# Cal.net
KiCad netlist of a schematic drawn in Altium Designer
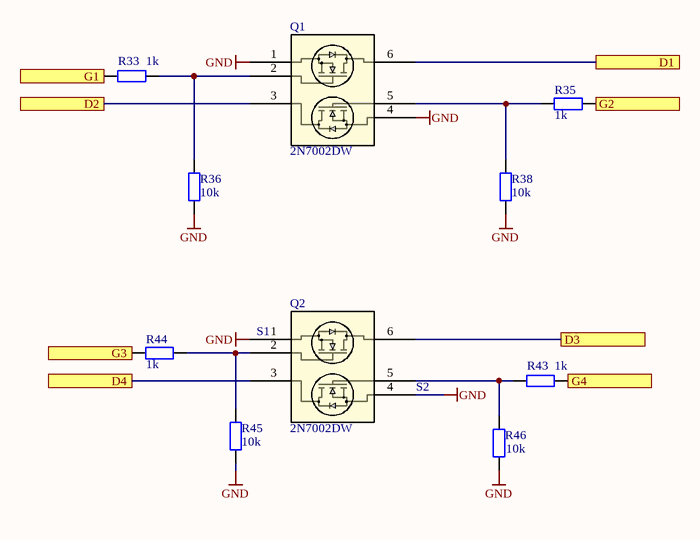
[diagram p0: Cal.SchDoc]

(export (version "E")
  (design (tool "Eeschema 10.0.6"))
  (components
    (comp (ref "Q1")
      (value "2N7002DW")
      (footprint "SC-88SC70-6SOT-363_419B-02_ONS_OSI")
      (description "Description")
      (fields (field (name "COPYRIGHT") "Copyright (C) 2026 Ultra Librarian. All rights reserved."))
      (libsource (lib "2N7002DW") (part "2N7002DW"))
    )
    (comp (ref "Q2")
      (value "2N7002DW")
      (footprint "SC-88SC70-6SOT-363_419B-02_ONS_OSI")
      (description "Description")
      (fields (field (name "COPYRIGHT") "Copyright (C) 2026 Ultra Librarian. All rights reserved."))
      (libsource (lib "2N7002DW") (part "2N7002DW"))
    )
    (comp (ref "R33")
      (value "1k")
      (footprint "C1206-KUE")
      (description "Resistor SMD")
      (fields (field (name "MANUFACTURER") "AVX") (field (name "PUBLISHER") "Altium Limited"))
      (libsource (lib "") (part "ResistorSMD_1"))
    )
    (comp (ref "R35")
      (value "1k")
      (footprint "C1206-KUE")
      (description "Resistor SMD")
      (fields (field (name "MANUFACTURER") "AVX") (field (name "PUBLISHER") "Altium Limited"))
      (libsource (lib "") (part "ResistorSMD_2"))
    )
    (comp (ref "R36")
      (value "10k")
      (footprint "C1206-KUE")
      (description "Resistor SMD")
      (fields (field (name "MANUFACTURER") "AVX") (field (name "PUBLISHER") "Altium Limited"))
      (libsource (lib "ExtrapartsKUE_V01") (part "ResistorSMD"))
    )
    (comp (ref "R38")
      (value "10k")
      (footprint "C1206-KUE")
      (description "Resistor SMD")
      (fields (field (name "MANUFACTURER") "AVX") (field (name "PUBLISHER") "Altium Limited"))
      (libsource (lib "ExtrapartsKUE_V01") (part "ResistorSMD"))
    )
    (comp (ref "R43")
      (value "1k")
      (footprint "C1206-KUE")
      (description "Resistor SMD")
      (fields (field (name "MANUFACTURER") "AVX") (field (name "PUBLISHER") "Altium Limited"))
      (libsource (lib "") (part "ResistorSMD_1"))
    )
    (comp (ref "R44")
      (value "1k")
      (footprint "C1206-KUE")
      (description "Resistor SMD")
      (fields (field (name "MANUFACTURER") "AVX") (field (name "PUBLISHER") "Altium Limited"))
      (libsource (lib "") (part "ResistorSMD_1"))
    )
    (comp (ref "R45")
      (value "10k")
      (footprint "C1206-KUE")
      (description "Resistor SMD")
      (fields (field (name "MANUFACTURER") "AVX") (field (name "PUBLISHER") "Altium Limited"))
      (libsource (lib "ExtrapartsKUE_V01") (part "ResistorSMD"))
    )
    (comp (ref "R46")
      (value "10k")
      (footprint "C1206-KUE")
      (description "Resistor SMD")
      (fields (field (name "MANUFACTURER") "AVX") (field (name "PUBLISHER") "Altium Limited"))
      (libsource (lib "ExtrapartsKUE_V01") (part "ResistorSMD"))
    )
  )
  (nets
    (net (code "1") (name "/D1") (class "Default")
      (node (ref "Q1") (pin "6") (pinfunction "6_6") (pintype "passive"))
    )
    (net (code "2") (name "/D2") (class "Default")
      (node (ref "Q1") (pin "3") (pinfunction "3_3") (pintype "passive"))
    )
    (net (code "3") (name "/D3") (class "Default")
      (node (ref "Q2") (pin "6") (pinfunction "6_6") (pintype "passive"))
    )
    (net (code "4") (name "/D4") (class "Default")
      (node (ref "Q2") (pin "3") (pinfunction "3_3") (pintype "passive"))
    )
    (net (code "5") (name "/G1") (class "Default")
      (node (ref "R33") (pin "2") (pinfunction "2_2") (pintype "passive"))
    )
    (net (code "6") (name "/G2") (class "Default")
      (node (ref "R35") (pin "2") (pinfunction "2_2") (pintype "passive"))
    )
    (net (code "7") (name "/G3") (class "Default")
      (node (ref "R44") (pin "2") (pinfunction "2_2") (pintype "passive"))
    )
    (net (code "8") (name "/G4") (class "Default")
      (node (ref "R43") (pin "1") (pinfunction "1_1") (pintype "passive"))
    )
    (net (code "9") (name "GND") (class "Default")
      (node (ref "Q1") (pin "1") (pinfunction "1_1") (pintype "passive"))
      (node (ref "Q1") (pin "4") (pinfunction "4_4") (pintype "passive"))
      (node (ref "Q2") (pin "1") (pinfunction "1_1") (pintype "passive"))
      (node (ref "Q2") (pin "4") (pinfunction "4_4") (pintype "passive"))
      (node (ref "R36") (pin "2") (pinfunction "2_2") (pintype "passive"))
      (node (ref "R38") (pin "2") (pinfunction "2_2") (pintype "passive"))
      (node (ref "R45") (pin "2") (pinfunction "2_2") (pintype "passive"))
      (node (ref "R46") (pin "2") (pinfunction "2_2") (pintype "passive"))
    )
    (net (code "10") (name "Net-(Q1-Pad2)") (class "Default")
      (node (ref "Q1") (pin "2") (pinfunction "2_2") (pintype "passive"))
      (node (ref "R33") (pin "1") (pinfunction "1_1") (pintype "passive"))
      (node (ref "R36") (pin "1") (pinfunction "1_1") (pintype "passive"))
    )
    (net (code "11") (name "Net-(Q1-Pad5)") (class "Default")
      (node (ref "Q1") (pin "5") (pinfunction "5_5") (pintype "passive"))
      (node (ref "R35") (pin "1") (pinfunction "1_1") (pintype "passive"))
      (node (ref "R38") (pin "1") (pinfunction "1_1") (pintype "passive"))
    )
    (net (code "12") (name "Net-(Q2-Pad2)") (class "Default")
      (node (ref "Q2") (pin "2") (pinfunction "2_2") (pintype "passive"))
      (node (ref "R44") (pin "1") (pinfunction "1_1") (pintype "passive"))
      (node (ref "R45") (pin "1") (pinfunction "1_1") (pintype "passive"))
    )
    (net (code "13") (name "Net-(Q2-Pad5)") (class "Default")
      (node (ref "Q2") (pin "5") (pinfunction "5_5") (pintype "passive"))
      (node (ref "R43") (pin "2") (pinfunction "2_2") (pintype "passive"))
      (node (ref "R46") (pin "1") (pinfunction "1_1") (pintype "passive"))
    )
  )
)
